# board_fertig.net
KiCad netlist of a schematic drawn in EAGLE
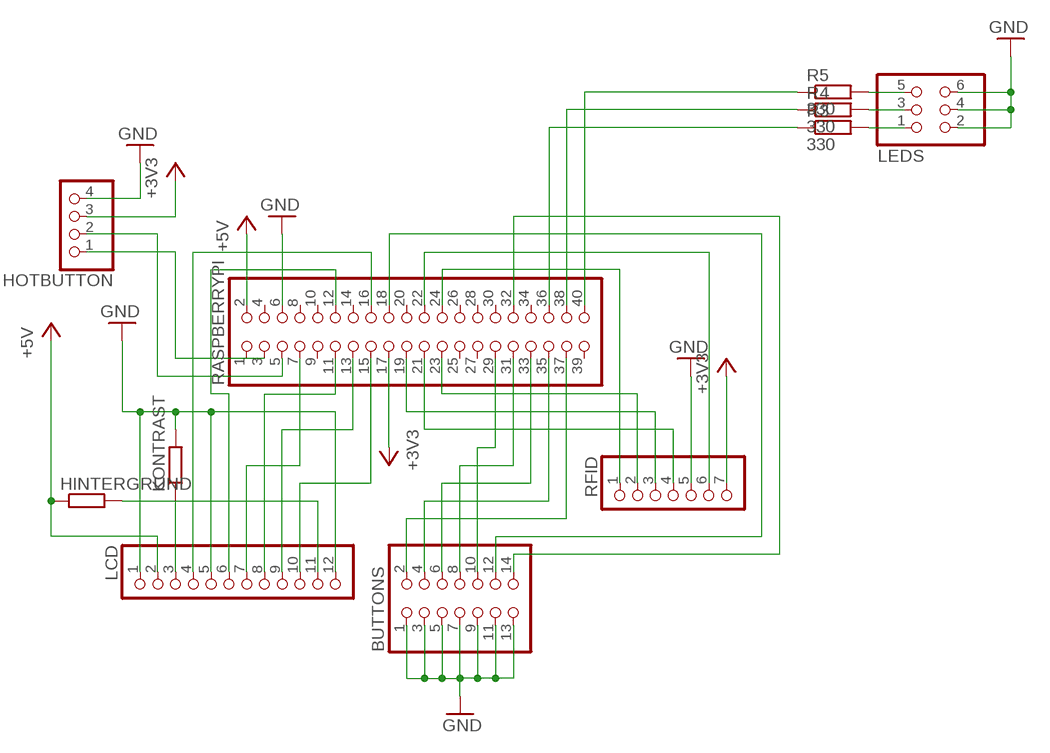
[diagram p0: schematic, sheet 1]

(export (version "E")
  (design (tool "Eeschema 10.0.6"))
  (components
    (comp (ref "BUTTONS")
      (value "PINHD-2X7")
      (footprint "eagle-import:2X07")
      (libsource (lib "eagle-import") (part "PINHD-2X7"))
    )
    (comp (ref "HINTERGRUND")
      (value "R-EU_0207/10")
      (footprint "eagle-import:0207_10")
      (libsource (lib "eagle-import") (part "R-EU_0207/10"))
    )
    (comp (ref "HOTBUTTON")
      (value "PINHD-1X4")
      (footprint "eagle-import:1X04")
      (libsource (lib "eagle-import") (part "PINHD-1X4"))
    )
    (comp (ref "KONTRAST")
      (value "R-EU_0207/10")
      (footprint "eagle-import:0207_10")
      (libsource (lib "eagle-import") (part "R-EU_0207/10"))
    )
    (comp (ref "LCD")
      (value "PINHD-1X12")
      (footprint "eagle-import:1X12")
      (libsource (lib "eagle-import") (part "PINHD-1X12"))
    )
    (comp (ref "LEDS")
      (value "PINHD-2X3")
      (footprint "eagle-import:2X03")
      (libsource (lib "eagle-import") (part "PINHD-2X3"))
    )
    (comp (ref "R3")
      (value "330")
      (footprint "eagle-import:0207_10")
      (libsource (lib "eagle-import") (part "R-EU_0207/10"))
    )
    (comp (ref "R4")
      (value "330")
      (footprint "eagle-import:0207_10")
      (libsource (lib "eagle-import") (part "R-EU_0207/10"))
    )
    (comp (ref "R5")
      (value "330")
      (footprint "eagle-import:0207_10")
      (libsource (lib "eagle-import") (part "R-EU_0207/10"))
    )
    (comp (ref "RASPBERRYPI")
      (value "PINHD-2X20")
      (footprint "eagle-import:2X20")
      (libsource (lib "eagle-import") (part "PINHD-2X20"))
    )
    (comp (ref "RFID")
      (value "PINHD-1X7")
      (footprint "eagle-import:1X07")
      (libsource (lib "eagle-import") (part "PINHD-1X7"))
    )
  )
  (nets
    (net (code "1") (name "+3V3") (class "Default")
      (node (ref "HOTBUTTON") (pin "3") (pinfunction "3_3") (pintype "passive"))
      (node (ref "RASPBERRYPI") (pin "17") (pinfunction "17_17") (pintype "passive"))
      (node (ref "RFID") (pin "7") (pinfunction "7_7") (pintype "passive"))
    )
    (net (code "2") (name "+5V") (class "Default")
      (node (ref "HINTERGRUND") (pin "1") (pinfunction "1_1") (pintype "passive"))
      (node (ref "LCD") (pin "2") (pinfunction "2_2") (pintype "passive"))
      (node (ref "RASPBERRYPI") (pin "2") (pinfunction "2_2") (pintype "passive"))
    )
    (net (code "3") (name "GND") (class "Default")
      (node (ref "BUTTONS") (pin "1") (pinfunction "1_1") (pintype "passive"))
      (node (ref "BUTTONS") (pin "11") (pinfunction "11_11") (pintype "passive"))
      (node (ref "BUTTONS") (pin "13") (pinfunction "13_13") (pintype "passive"))
      (node (ref "BUTTONS") (pin "3") (pinfunction "3_3") (pintype "passive"))
      (node (ref "BUTTONS") (pin "5") (pinfunction "5_5") (pintype "passive"))
      (node (ref "BUTTONS") (pin "7") (pinfunction "7_7") (pintype "passive"))
      (node (ref "BUTTONS") (pin "9") (pinfunction "9_9") (pintype "passive"))
      (node (ref "HOTBUTTON") (pin "4") (pinfunction "4_4") (pintype "passive"))
      (node (ref "KONTRAST") (pin "2") (pinfunction "2_2") (pintype "passive"))
      (node (ref "LCD") (pin "1") (pinfunction "1_1") (pintype "passive"))
      (node (ref "LCD") (pin "12") (pinfunction "12_12") (pintype "passive"))
      (node (ref "LCD") (pin "5") (pinfunction "5_5") (pintype "passive"))
      (node (ref "LEDS") (pin "2") (pinfunction "2_2") (pintype "passive"))
      (node (ref "LEDS") (pin "4") (pinfunction "4_4") (pintype "passive"))
      (node (ref "LEDS") (pin "6") (pinfunction "6_6") (pintype "passive"))
      (node (ref "RASPBERRYPI") (pin "6") (pinfunction "6_6") (pintype "passive"))
      (node (ref "RFID") (pin "5") (pinfunction "5_5") (pintype "passive"))
    )
    (net (code "4") (name "Net-(BUTTONS-Pad2)") (class "Default")
      (node (ref "BUTTONS") (pin "2") (pinfunction "2_2") (pintype "passive"))
      (node (ref "RASPBERRYPI") (pin "37") (pinfunction "37_37") (pintype "passive"))
    )
    (net (code "5") (name "Net-(BUTTONS-Pad4)") (class "Default")
      (node (ref "BUTTONS") (pin "4") (pinfunction "4_4") (pintype "passive"))
      (node (ref "RASPBERRYPI") (pin "35") (pinfunction "35_35") (pintype "passive"))
    )
    (net (code "6") (name "Net-(BUTTONS-Pad6)") (class "Default")
      (node (ref "BUTTONS") (pin "6") (pinfunction "6_6") (pintype "passive"))
      (node (ref "RASPBERRYPI") (pin "33") (pinfunction "33_33") (pintype "passive"))
    )
    (net (code "7") (name "Net-(BUTTONS-Pad8)") (class "Default")
      (node (ref "BUTTONS") (pin "8") (pinfunction "8_8") (pintype "passive"))
      (node (ref "RASPBERRYPI") (pin "31") (pinfunction "31_31") (pintype "passive"))
    )
    (net (code "8") (name "Net-(BUTTONS-Pad10)") (class "Default")
      (node (ref "BUTTONS") (pin "10") (pinfunction "10_10") (pintype "passive"))
      (node (ref "RASPBERRYPI") (pin "29") (pinfunction "29_29") (pintype "passive"))
    )
    (net (code "9") (name "Net-(BUTTONS-Pad12)") (class "Default")
      (node (ref "BUTTONS") (pin "12") (pinfunction "12_12") (pintype "passive"))
      (node (ref "RASPBERRYPI") (pin "18") (pinfunction "18_18") (pintype "passive"))
    )
    (net (code "10") (name "Net-(BUTTONS-Pad14)") (class "Default")
      (node (ref "BUTTONS") (pin "14") (pinfunction "14_14") (pintype "passive"))
      (node (ref "RASPBERRYPI") (pin "32") (pinfunction "32_32") (pintype "passive"))
    )
    (net (code "11") (name "Net-(HINTERGRUND-Pad2)") (class "Default")
      (node (ref "HINTERGRUND") (pin "2") (pinfunction "2_2") (pintype "passive"))
      (node (ref "LCD") (pin "11") (pinfunction "11_11") (pintype "passive"))
    )
    (net (code "12") (name "Net-(HOTBUTTON-Pad1)") (class "Default")
      (node (ref "HOTBUTTON") (pin "1") (pinfunction "1_1") (pintype "passive"))
      (node (ref "RASPBERRYPI") (pin "3") (pinfunction "3_3") (pintype "passive"))
    )
    (net (code "13") (name "Net-(HOTBUTTON-Pad2)") (class "Default")
      (node (ref "HOTBUTTON") (pin "2") (pinfunction "2_2") (pintype "passive"))
      (node (ref "RASPBERRYPI") (pin "5") (pinfunction "5_5") (pintype "passive"))
    )
    (net (code "14") (name "Net-(KONTRAST-Pad1)") (class "Default")
      (node (ref "KONTRAST") (pin "1") (pinfunction "1_1") (pintype "passive"))
      (node (ref "LCD") (pin "3") (pinfunction "3_3") (pintype "passive"))
    )
    (net (code "15") (name "Net-(LCD-Pad4)") (class "Default")
      (node (ref "LCD") (pin "4") (pinfunction "4_4") (pintype "passive"))
      (node (ref "RASPBERRYPI") (pin "16") (pinfunction "16_16") (pintype "passive"))
    )
    (net (code "16") (name "Net-(LCD-Pad6)") (class "Default")
      (node (ref "LCD") (pin "6") (pinfunction "6_6") (pintype "passive"))
      (node (ref "RASPBERRYPI") (pin "12") (pinfunction "12_12") (pintype "passive"))
    )
    (net (code "17") (name "Net-(LCD-Pad7)") (class "Default")
      (node (ref "LCD") (pin "7") (pinfunction "7_7") (pintype "passive"))
      (node (ref "RASPBERRYPI") (pin "7") (pinfunction "7_7") (pintype "passive"))
    )
    (net (code "18") (name "Net-(LCD-Pad8)") (class "Default")
      (node (ref "LCD") (pin "8") (pinfunction "8_8") (pintype "passive"))
      (node (ref "RASPBERRYPI") (pin "11") (pinfunction "11_11") (pintype "passive"))
    )
    (net (code "19") (name "Net-(LCD-Pad9)") (class "Default")
      (node (ref "LCD") (pin "9") (pinfunction "9_9") (pintype "passive"))
      (node (ref "RASPBERRYPI") (pin "13") (pinfunction "13_13") (pintype "passive"))
    )
    (net (code "20") (name "Net-(LCD-Pad10)") (class "Default")
      (node (ref "LCD") (pin "10") (pinfunction "10_10") (pintype "passive"))
      (node (ref "RASPBERRYPI") (pin "15") (pinfunction "15_15") (pintype "passive"))
    )
    (net (code "21") (name "Net-(LEDS-Pad1)") (class "Default")
      (node (ref "LEDS") (pin "1") (pinfunction "1_1") (pintype "passive"))
      (node (ref "R3") (pin "2") (pinfunction "2_2") (pintype "passive"))
    )
    (net (code "22") (name "Net-(LEDS-Pad3)") (class "Default")
      (node (ref "LEDS") (pin "3") (pinfunction "3_3") (pintype "passive"))
      (node (ref "R4") (pin "2") (pinfunction "2_2") (pintype "passive"))
    )
    (net (code "23") (name "Net-(LEDS-Pad5)") (class "Default")
      (node (ref "LEDS") (pin "5") (pinfunction "5_5") (pintype "passive"))
      (node (ref "R5") (pin "2") (pinfunction "2_2") (pintype "passive"))
    )
    (net (code "24") (name "Net-(R3-Pad1)") (class "Default")
      (node (ref "R3") (pin "1") (pinfunction "1_1") (pintype "passive"))
      (node (ref "RASPBERRYPI") (pin "36") (pinfunction "36_36") (pintype "passive"))
    )
    (net (code "25") (name "Net-(R4-Pad1)") (class "Default")
      (node (ref "R4") (pin "1") (pinfunction "1_1") (pintype "passive"))
      (node (ref "RASPBERRYPI") (pin "38") (pinfunction "38_38") (pintype "passive"))
    )
    (net (code "26") (name "Net-(R5-Pad1)") (class "Default")
      (node (ref "R5") (pin "1") (pinfunction "1_1") (pintype "passive"))
      (node (ref "RASPBERRYPI") (pin "40") (pinfunction "40_40") (pintype "passive"))
    )
    (net (code "27") (name "Net-(RASPBERRYPI-Pad19)") (class "Default")
      (node (ref "RASPBERRYPI") (pin "19") (pinfunction "19_19") (pintype "passive"))
      (node (ref "RFID") (pin "3") (pinfunction "3_3") (pintype "passive"))
    )
    (net (code "28") (name "Net-(RASPBERRYPI-Pad21)") (class "Default")
      (node (ref "RASPBERRYPI") (pin "21") (pinfunction "21_21") (pintype "passive"))
      (node (ref "RFID") (pin "4") (pinfunction "4_4") (pintype "passive"))
    )
    (net (code "29") (name "Net-(RASPBERRYPI-Pad22)") (class "Default")
      (node (ref "RASPBERRYPI") (pin "22") (pinfunction "22_22") (pintype "passive"))
      (node (ref "RFID") (pin "6") (pinfunction "6_6") (pintype "passive"))
    )
    (net (code "30") (name "Net-(RASPBERRYPI-Pad23)") (class "Default")
      (node (ref "RASPBERRYPI") (pin "23") (pinfunction "23_23") (pintype "passive"))
      (node (ref "RFID") (pin "2") (pinfunction "2_2") (pintype "passive"))
    )
    (net (code "31") (name "Net-(RASPBERRYPI-Pad24)") (class "Default")
      (node (ref "RASPBERRYPI") (pin "24") (pinfunction "24_24") (pintype "passive"))
      (node (ref "RFID") (pin "1") (pinfunction "1_1") (pintype "passive"))
    )
    (net (code "32") (name "unconnected-(RASPBERRYPI-Pad1)") (class "Default")
      (node (ref "RASPBERRYPI") (pin "1") (pinfunction "1_1") (pintype "passive"))
    )
    (net (code "33") (name "unconnected-(RASPBERRYPI-Pad4)") (class "Default")
      (node (ref "RASPBERRYPI") (pin "4") (pinfunction "4_4") (pintype "passive"))
    )
    (net (code "34") (name "unconnected-(RASPBERRYPI-Pad8)") (class "Default")
      (node (ref "RASPBERRYPI") (pin "8") (pinfunction "8_8") (pintype "passive"))
    )
    (net (code "35") (name "unconnected-(RASPBERRYPI-Pad9)") (class "Default")
      (node (ref "RASPBERRYPI") (pin "9") (pinfunction "9_9") (pintype "passive"))
    )
    (net (code "36") (name "unconnected-(RASPBERRYPI-Pad10)") (class "Default")
      (node (ref "RASPBERRYPI") (pin "10") (pinfunction "10_10") (pintype "passive"))
    )
    (net (code "37") (name "unconnected-(RASPBERRYPI-Pad14)") (class "Default")
      (node (ref "RASPBERRYPI") (pin "14") (pinfunction "14_14") (pintype "passive"))
    )
    (net (code "38") (name "unconnected-(RASPBERRYPI-Pad20)") (class "Default")
      (node (ref "RASPBERRYPI") (pin "20") (pinfunction "20_20") (pintype "passive"))
    )
    (net (code "39") (name "unconnected-(RASPBERRYPI-Pad25)") (class "Default")
      (node (ref "RASPBERRYPI") (pin "25") (pinfunction "25_25") (pintype "passive"))
    )
    (net (code "40") (name "unconnected-(RASPBERRYPI-Pad26)") (class "Default")
      (node (ref "RASPBERRYPI") (pin "26") (pinfunction "26_26") (pintype "passive"))
    )
    (net (code "41") (name "unconnected-(RASPBERRYPI-Pad27)") (class "Default")
      (node (ref "RASPBERRYPI") (pin "27") (pinfunction "27_27") (pintype "passive"))
    )
    (net (code "42") (name "unconnected-(RASPBERRYPI-Pad28)") (class "Default")
      (node (ref "RASPBERRYPI") (pin "28") (pinfunction "28_28") (pintype "passive"))
    )
    (net (code "43") (name "unconnected-(RASPBERRYPI-Pad30)") (class "Default")
      (node (ref "RASPBERRYPI") (pin "30") (pinfunction "30_30") (pintype "passive"))
    )
    (net (code "44") (name "unconnected-(RASPBERRYPI-Pad34)") (class "Default")
      (node (ref "RASPBERRYPI") (pin "34") (pinfunction "34_34") (pintype "passive"))
    )
    (net (code "45") (name "unconnected-(RASPBERRYPI-Pad39)") (class "Default")
      (node (ref "RASPBERRYPI") (pin "39") (pinfunction "39_39") (pintype "passive"))
    )
  )
)
